# board.net
KiCad netlist of a schematic drawn in EAGLE
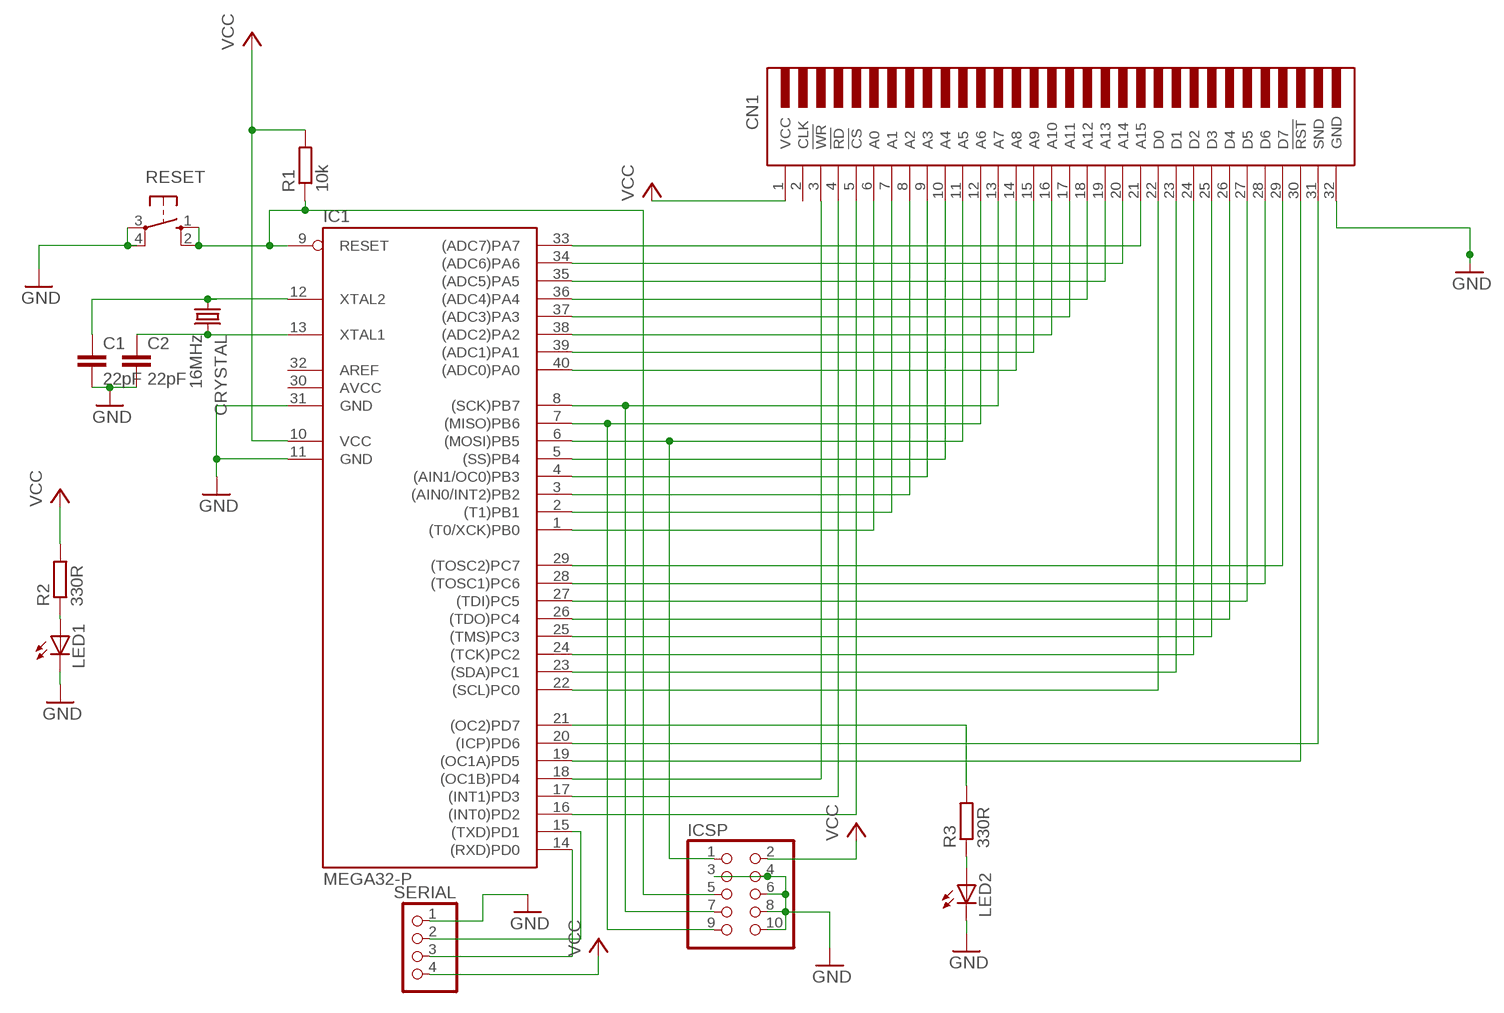
[diagram p0: schematic, sheet 1]

(export (version "E")
  (design (tool "Eeschema 10.0.6"))
  (components
    (comp (ref "C1")
      (value "22pF")
      (footprint "eagle-import:C050-025X075")
      (libsource (lib "eagle-import") (part "C-EU050-025X075"))
    )
    (comp (ref "C2")
      (value "22pF")
      (footprint "eagle-import:C050-025X075")
      (libsource (lib "eagle-import") (part "C-EU050-025X075"))
    )
    (comp (ref "CN1")
      (value "GBCONN")
      (footprint "eagle-import:GBCONN")
      (libsource (lib "eagle-import") (part "GBCONN"))
    )
    (comp (ref "CRYSTAL")
      (value "16MHz")
      (footprint "eagle-import:HC49_S")
      (libsource (lib "eagle-import") (part "CRYSTALHC49S"))
    )
    (comp (ref "IC1")
      (value "MEGA32-P")
      (footprint "eagle-import:DIL40")
      (fields (field (name "MPN") "ATMEGA32-16PU"))
      (libsource (lib "eagle-import") (part "MEGA32-P"))
    )
    (comp (ref "ICSP")
      (value "PINHD-2X5")
      (footprint "eagle-import:2X05")
      (libsource (lib "eagle-import") (part "PINHD-2X5"))
    )
    (comp (ref "LED1")
      (value "LED3MM")
      (footprint "eagle-import:LED3MM")
      (libsource (lib "eagle-import") (part "LED3MM"))
    )
    (comp (ref "LED2")
      (value "LED3MM")
      (footprint "eagle-import:LED3MM")
      (libsource (lib "eagle-import") (part "LED3MM"))
    )
    (comp (ref "R1")
      (value "10k")
      (footprint "eagle-import:0204_7")
      (libsource (lib "eagle-import") (part "R-EU_0204/7"))
    )
    (comp (ref "R2")
      (value "330R")
      (footprint "eagle-import:0204_7")
      (libsource (lib "eagle-import") (part "R-EU_0204/7"))
    )
    (comp (ref "R3")
      (value "330R")
      (footprint "eagle-import:0204_7")
      (libsource (lib "eagle-import") (part "R-EU_0204/7"))
    )
    (comp (ref "RESET")
      (value "10-XX")
      (footprint "eagle-import:B3F-10XX")
      (fields (field (name "MPN") "B3F-1000"))
      (libsource (lib "eagle-import") (part "10-XX"))
    )
    (comp (ref "SERIAL")
      (value "PINHD-1X4/90")
      (footprint "eagle-import:1X04_90")
      (libsource (lib "eagle-import") (part "PINHD-1X4/90"))
    )
  )
  (nets
    (net (code "1") (name "/AVCC") (class "Default")
      (node (ref "IC1") (pin "30") (pinfunction "AVCC_30") (pintype "power_in"))
    )
    (net (code "2") (name "GND") (class "Default")
      (node (ref "C1") (pin "2") (pinfunction "2_2") (pintype "passive"))
      (node (ref "C2") (pin "2") (pinfunction "2_2") (pintype "passive"))
      (node (ref "CN1") (pin "32") (pinfunction "GND_32") (pintype "power_in"))
      (node (ref "IC1") (pin "11") (pinfunction "GND_11") (pintype "power_in"))
      (node (ref "IC1") (pin "31") (pinfunction "GND_31") (pintype "power_in"))
      (node (ref "ICSP") (pin "10") (pinfunction "10_10") (pintype "passive"))
      (node (ref "ICSP") (pin "3") (pinfunction "3_3") (pintype "passive"))
      (node (ref "ICSP") (pin "4") (pinfunction "4_4") (pintype "passive"))
      (node (ref "ICSP") (pin "6") (pinfunction "6_6") (pintype "passive"))
      (node (ref "ICSP") (pin "8") (pinfunction "8_8") (pintype "passive"))
      (node (ref "LED1") (pin "K") (pinfunction "C_K") (pintype "passive"))
      (node (ref "LED2") (pin "K") (pinfunction "C_K") (pintype "passive"))
      (node (ref "RESET") (pin "3") (pinfunction "P_3") (pintype "passive"))
      (node (ref "RESET") (pin "4") (pinfunction "P1_4") (pintype "passive"))
      (node (ref "SERIAL") (pin "1") (pinfunction "1_1") (pintype "passive"))
    )
    (net (code "3") (name "Net-(CN1-A0)") (class "Default")
      (node (ref "CN1") (pin "6") (pinfunction "A0_6") (pintype "output"))
      (node (ref "IC1") (pin "1") (pinfunction "(T0/XCK)PB0_1") (pintype "bidirectional"))
    )
    (net (code "4") (name "Net-(CN1-A1)") (class "Default")
      (node (ref "CN1") (pin "7") (pinfunction "A1_7") (pintype "output"))
      (node (ref "IC1") (pin "2") (pinfunction "(T1)PB1_2") (pintype "bidirectional"))
    )
    (net (code "5") (name "Net-(CN1-A2)") (class "Default")
      (node (ref "CN1") (pin "8") (pinfunction "A2_8") (pintype "output"))
      (node (ref "IC1") (pin "3") (pinfunction "(AIN0/INT2)PB2_3") (pintype "bidirectional"))
    )
    (net (code "6") (name "Net-(CN1-A3)") (class "Default")
      (node (ref "CN1") (pin "9") (pinfunction "A3_9") (pintype "output"))
      (node (ref "IC1") (pin "4") (pinfunction "(AIN1/OC0)PB3_4") (pintype "bidirectional"))
    )
    (net (code "7") (name "Net-(CN1-A4)") (class "Default")
      (node (ref "CN1") (pin "10") (pinfunction "A4_10") (pintype "output"))
      (node (ref "IC1") (pin "5") (pinfunction "(SS)PB4_5") (pintype "bidirectional"))
    )
    (net (code "8") (name "Net-(CN1-A5)") (class "Default")
      (node (ref "CN1") (pin "11") (pinfunction "A5_11") (pintype "output"))
      (node (ref "IC1") (pin "6") (pinfunction "(MOSI)PB5_6") (pintype "bidirectional"))
      (node (ref "ICSP") (pin "1") (pinfunction "1_1") (pintype "passive"))
    )
    (net (code "9") (name "Net-(CN1-A6)") (class "Default")
      (node (ref "CN1") (pin "12") (pinfunction "A6_12") (pintype "output"))
      (node (ref "IC1") (pin "7") (pinfunction "(MISO)PB6_7") (pintype "bidirectional"))
      (node (ref "ICSP") (pin "9") (pinfunction "9_9") (pintype "passive"))
    )
    (net (code "10") (name "Net-(CN1-A7)") (class "Default")
      (node (ref "CN1") (pin "13") (pinfunction "A7_13") (pintype "output"))
      (node (ref "IC1") (pin "8") (pinfunction "(SCK)PB7_8") (pintype "bidirectional"))
      (node (ref "ICSP") (pin "7") (pinfunction "7_7") (pintype "passive"))
    )
    (net (code "11") (name "Net-(CN1-A8)") (class "Default")
      (node (ref "CN1") (pin "14") (pinfunction "A8_14") (pintype "output"))
      (node (ref "IC1") (pin "40") (pinfunction "(ADC0)PA0_40") (pintype "bidirectional"))
    )
    (net (code "12") (name "Net-(CN1-A9)") (class "Default")
      (node (ref "CN1") (pin "15") (pinfunction "A9_15") (pintype "output"))
      (node (ref "IC1") (pin "39") (pinfunction "(ADC1)PA1_39") (pintype "bidirectional"))
    )
    (net (code "13") (name "Net-(CN1-A10)") (class "Default")
      (node (ref "CN1") (pin "16") (pinfunction "A10_16") (pintype "output"))
      (node (ref "IC1") (pin "38") (pinfunction "(ADC2)PA2_38") (pintype "bidirectional"))
    )
    (net (code "14") (name "Net-(CN1-A11)") (class "Default")
      (node (ref "CN1") (pin "17") (pinfunction "A11_17") (pintype "output"))
      (node (ref "IC1") (pin "37") (pinfunction "(ADC3)PA3_37") (pintype "bidirectional"))
    )
    (net (code "15") (name "Net-(CN1-A12)") (class "Default")
      (node (ref "CN1") (pin "18") (pinfunction "A12_18") (pintype "output"))
      (node (ref "IC1") (pin "36") (pinfunction "(ADC4)PA4_36") (pintype "bidirectional"))
    )
    (net (code "16") (name "Net-(CN1-A13)") (class "Default")
      (node (ref "CN1") (pin "19") (pinfunction "A13_19") (pintype "output"))
      (node (ref "IC1") (pin "35") (pinfunction "(ADC5)PA5_35") (pintype "bidirectional"))
    )
    (net (code "17") (name "Net-(CN1-A14)") (class "Default")
      (node (ref "CN1") (pin "20") (pinfunction "A14_20") (pintype "output"))
      (node (ref "IC1") (pin "34") (pinfunction "(ADC6)PA6_34") (pintype "bidirectional"))
    )
    (net (code "18") (name "Net-(CN1-A15)") (class "Default")
      (node (ref "CN1") (pin "21") (pinfunction "A15_21") (pintype "output"))
      (node (ref "IC1") (pin "33") (pinfunction "(ADC7)PA7_33") (pintype "bidirectional"))
    )
    (net (code "19") (name "Net-(CN1-D0)") (class "Default")
      (node (ref "CN1") (pin "22") (pinfunction "D0_22") (pintype "bidirectional"))
      (node (ref "IC1") (pin "22") (pinfunction "(SCL)PC0_22") (pintype "bidirectional"))
    )
    (net (code "20") (name "Net-(CN1-D1)") (class "Default")
      (node (ref "CN1") (pin "23") (pinfunction "D1_23") (pintype "bidirectional"))
      (node (ref "IC1") (pin "23") (pinfunction "(SDA)PC1_23") (pintype "bidirectional"))
    )
    (net (code "21") (name "Net-(CN1-D2)") (class "Default")
      (node (ref "CN1") (pin "24") (pinfunction "D2_24") (pintype "bidirectional"))
      (node (ref "IC1") (pin "24") (pinfunction "(TCK)PC2_24") (pintype "bidirectional"))
    )
    (net (code "22") (name "Net-(CN1-D3)") (class "Default")
      (node (ref "CN1") (pin "25") (pinfunction "D3_25") (pintype "bidirectional"))
      (node (ref "IC1") (pin "25") (pinfunction "(TMS)PC3_25") (pintype "bidirectional"))
    )
    (net (code "23") (name "Net-(CN1-D4)") (class "Default")
      (node (ref "CN1") (pin "26") (pinfunction "D4_26") (pintype "bidirectional"))
      (node (ref "IC1") (pin "26") (pinfunction "(TDO)PC4_26") (pintype "bidirectional"))
    )
    (net (code "24") (name "Net-(CN1-D5)") (class "Default")
      (node (ref "CN1") (pin "27") (pinfunction "D5_27") (pintype "bidirectional"))
      (node (ref "IC1") (pin "27") (pinfunction "(TDI)PC5_27") (pintype "bidirectional"))
    )
    (net (code "25") (name "Net-(CN1-D6)") (class "Default")
      (node (ref "CN1") (pin "28") (pinfunction "D6_28") (pintype "bidirectional"))
      (node (ref "IC1") (pin "28") (pinfunction "(TOSC1)PC6_28") (pintype "bidirectional"))
    )
    (net (code "26") (name "Net-(CN1-D7)") (class "Default")
      (node (ref "CN1") (pin "29") (pinfunction "D7_29") (pintype "bidirectional"))
      (node (ref "IC1") (pin "29") (pinfunction "(TOSC2)PC7_29") (pintype "bidirectional"))
    )
    (net (code "27") (name "Net-(CN1-SND)") (class "Default")
      (node (ref "CN1") (pin "31") (pinfunction "SND_31") (pintype "bidirectional"))
      (node (ref "IC1") (pin "20") (pinfunction "(ICP)PD6_20") (pintype "bidirectional"))
    )
    (net (code "28") (name "Net-(CN1-~{CS})") (class "Default")
      (node (ref "CN1") (pin "5") (pinfunction "~{CS}_5") (pintype "output"))
      (node (ref "IC1") (pin "16") (pinfunction "(INT0)PD2_16") (pintype "bidirectional"))
    )
    (net (code "29") (name "Net-(CN1-~{RD})") (class "Default")
      (node (ref "CN1") (pin "4") (pinfunction "~{RD}_4") (pintype "output"))
      (node (ref "IC1") (pin "17") (pinfunction "(INT1)PD3_17") (pintype "bidirectional"))
    )
    (net (code "30") (name "Net-(CN1-~{RST})") (class "Default")
      (node (ref "CN1") (pin "30") (pinfunction "~{RST}_30") (pintype "bidirectional"))
      (node (ref "IC1") (pin "19") (pinfunction "(OC1A)PD5_19") (pintype "bidirectional"))
    )
    (net (code "31") (name "Net-(CN1-~{WR})") (class "Default")
      (node (ref "CN1") (pin "3") (pinfunction "~{WR}_3") (pintype "output"))
      (node (ref "IC1") (pin "18") (pinfunction "(OC1B)PD4_18") (pintype "bidirectional"))
    )
    (net (code "32") (name "Net-(IC1-(OC2)PD7)") (class "Default")
      (node (ref "IC1") (pin "21") (pinfunction "(OC2)PD7_21") (pintype "bidirectional"))
      (node (ref "R3") (pin "2") (pinfunction "2_2") (pintype "passive"))
    )
    (net (code "33") (name "Net-(IC1-(RXD)PD0)") (class "Default")
      (node (ref "IC1") (pin "14") (pinfunction "(RXD)PD0_14") (pintype "bidirectional"))
      (node (ref "SERIAL") (pin "3") (pinfunction "3_3") (pintype "passive"))
    )
    (net (code "34") (name "Net-(IC1-(TXD)PD1)") (class "Default")
      (node (ref "IC1") (pin "15") (pinfunction "(TXD)PD1_15") (pintype "bidirectional"))
      (node (ref "SERIAL") (pin "2") (pinfunction "2_2") (pintype "passive"))
    )
    (net (code "35") (name "Net-(IC1-RESET)") (class "Default")
      (node (ref "IC1") (pin "9") (pinfunction "RESET_9") (pintype "input"))
      (node (ref "ICSP") (pin "5") (pinfunction "5_5") (pintype "passive"))
      (node (ref "R1") (pin "1") (pinfunction "1_1") (pintype "passive"))
      (node (ref "RESET") (pin "1") (pinfunction "S_1") (pintype "passive"))
      (node (ref "RESET") (pin "2") (pinfunction "S1_2") (pintype "passive"))
    )
    (net (code "36") (name "Net-(IC1-XTAL1)") (class "Default")
      (node (ref "C2") (pin "1") (pinfunction "1_1") (pintype "passive"))
      (node (ref "CRYSTAL") (pin "2") (pinfunction "2_2") (pintype "passive"))
      (node (ref "IC1") (pin "13") (pinfunction "XTAL1_13") (pintype "bidirectional"))
    )
    (net (code "37") (name "Net-(IC1-XTAL2)") (class "Default")
      (node (ref "C1") (pin "1") (pinfunction "1_1") (pintype "passive"))
      (node (ref "CRYSTAL") (pin "1") (pinfunction "1_1") (pintype "passive"))
      (node (ref "IC1") (pin "12") (pinfunction "XTAL2_12") (pintype "bidirectional"))
    )
    (net (code "38") (name "Net-(LED1-PadA)") (class "Default")
      (node (ref "LED1") (pin "A") (pinfunction "A_A") (pintype "passive"))
      (node (ref "R2") (pin "1") (pinfunction "1_1") (pintype "passive"))
    )
    (net (code "39") (name "Net-(LED2-PadA)") (class "Default")
      (node (ref "LED2") (pin "A") (pinfunction "A_A") (pintype "passive"))
      (node (ref "R3") (pin "1") (pinfunction "1_1") (pintype "passive"))
    )
    (net (code "40") (name "VCC") (class "Default")
      (node (ref "CN1") (pin "1") (pinfunction "VCC_1") (pintype "power_in"))
      (node (ref "IC1") (pin "10") (pinfunction "VCC_10") (pintype "power_in"))
      (node (ref "ICSP") (pin "2") (pinfunction "2_2") (pintype "passive"))
      (node (ref "R1") (pin "2") (pinfunction "2_2") (pintype "passive"))
      (node (ref "R2") (pin "2") (pinfunction "2_2") (pintype "passive"))
      (node (ref "SERIAL") (pin "4") (pinfunction "4_4") (pintype "passive"))
    )
    (net (code "41") (name "unconnected-(CN1-CLK-Pad2)") (class "Default")
      (node (ref "CN1") (pin "2") (pinfunction "CLK_2") (pintype "output"))
    )
    (net (code "42") (name "unconnected-(IC1-AREF-Pad32)") (class "Default")
      (node (ref "IC1") (pin "32") (pinfunction "AREF_32") (pintype "passive"))
    )
  )
)
